# picoWiCopter.net
KiCad netlist of a schematic drawn in EAGLE
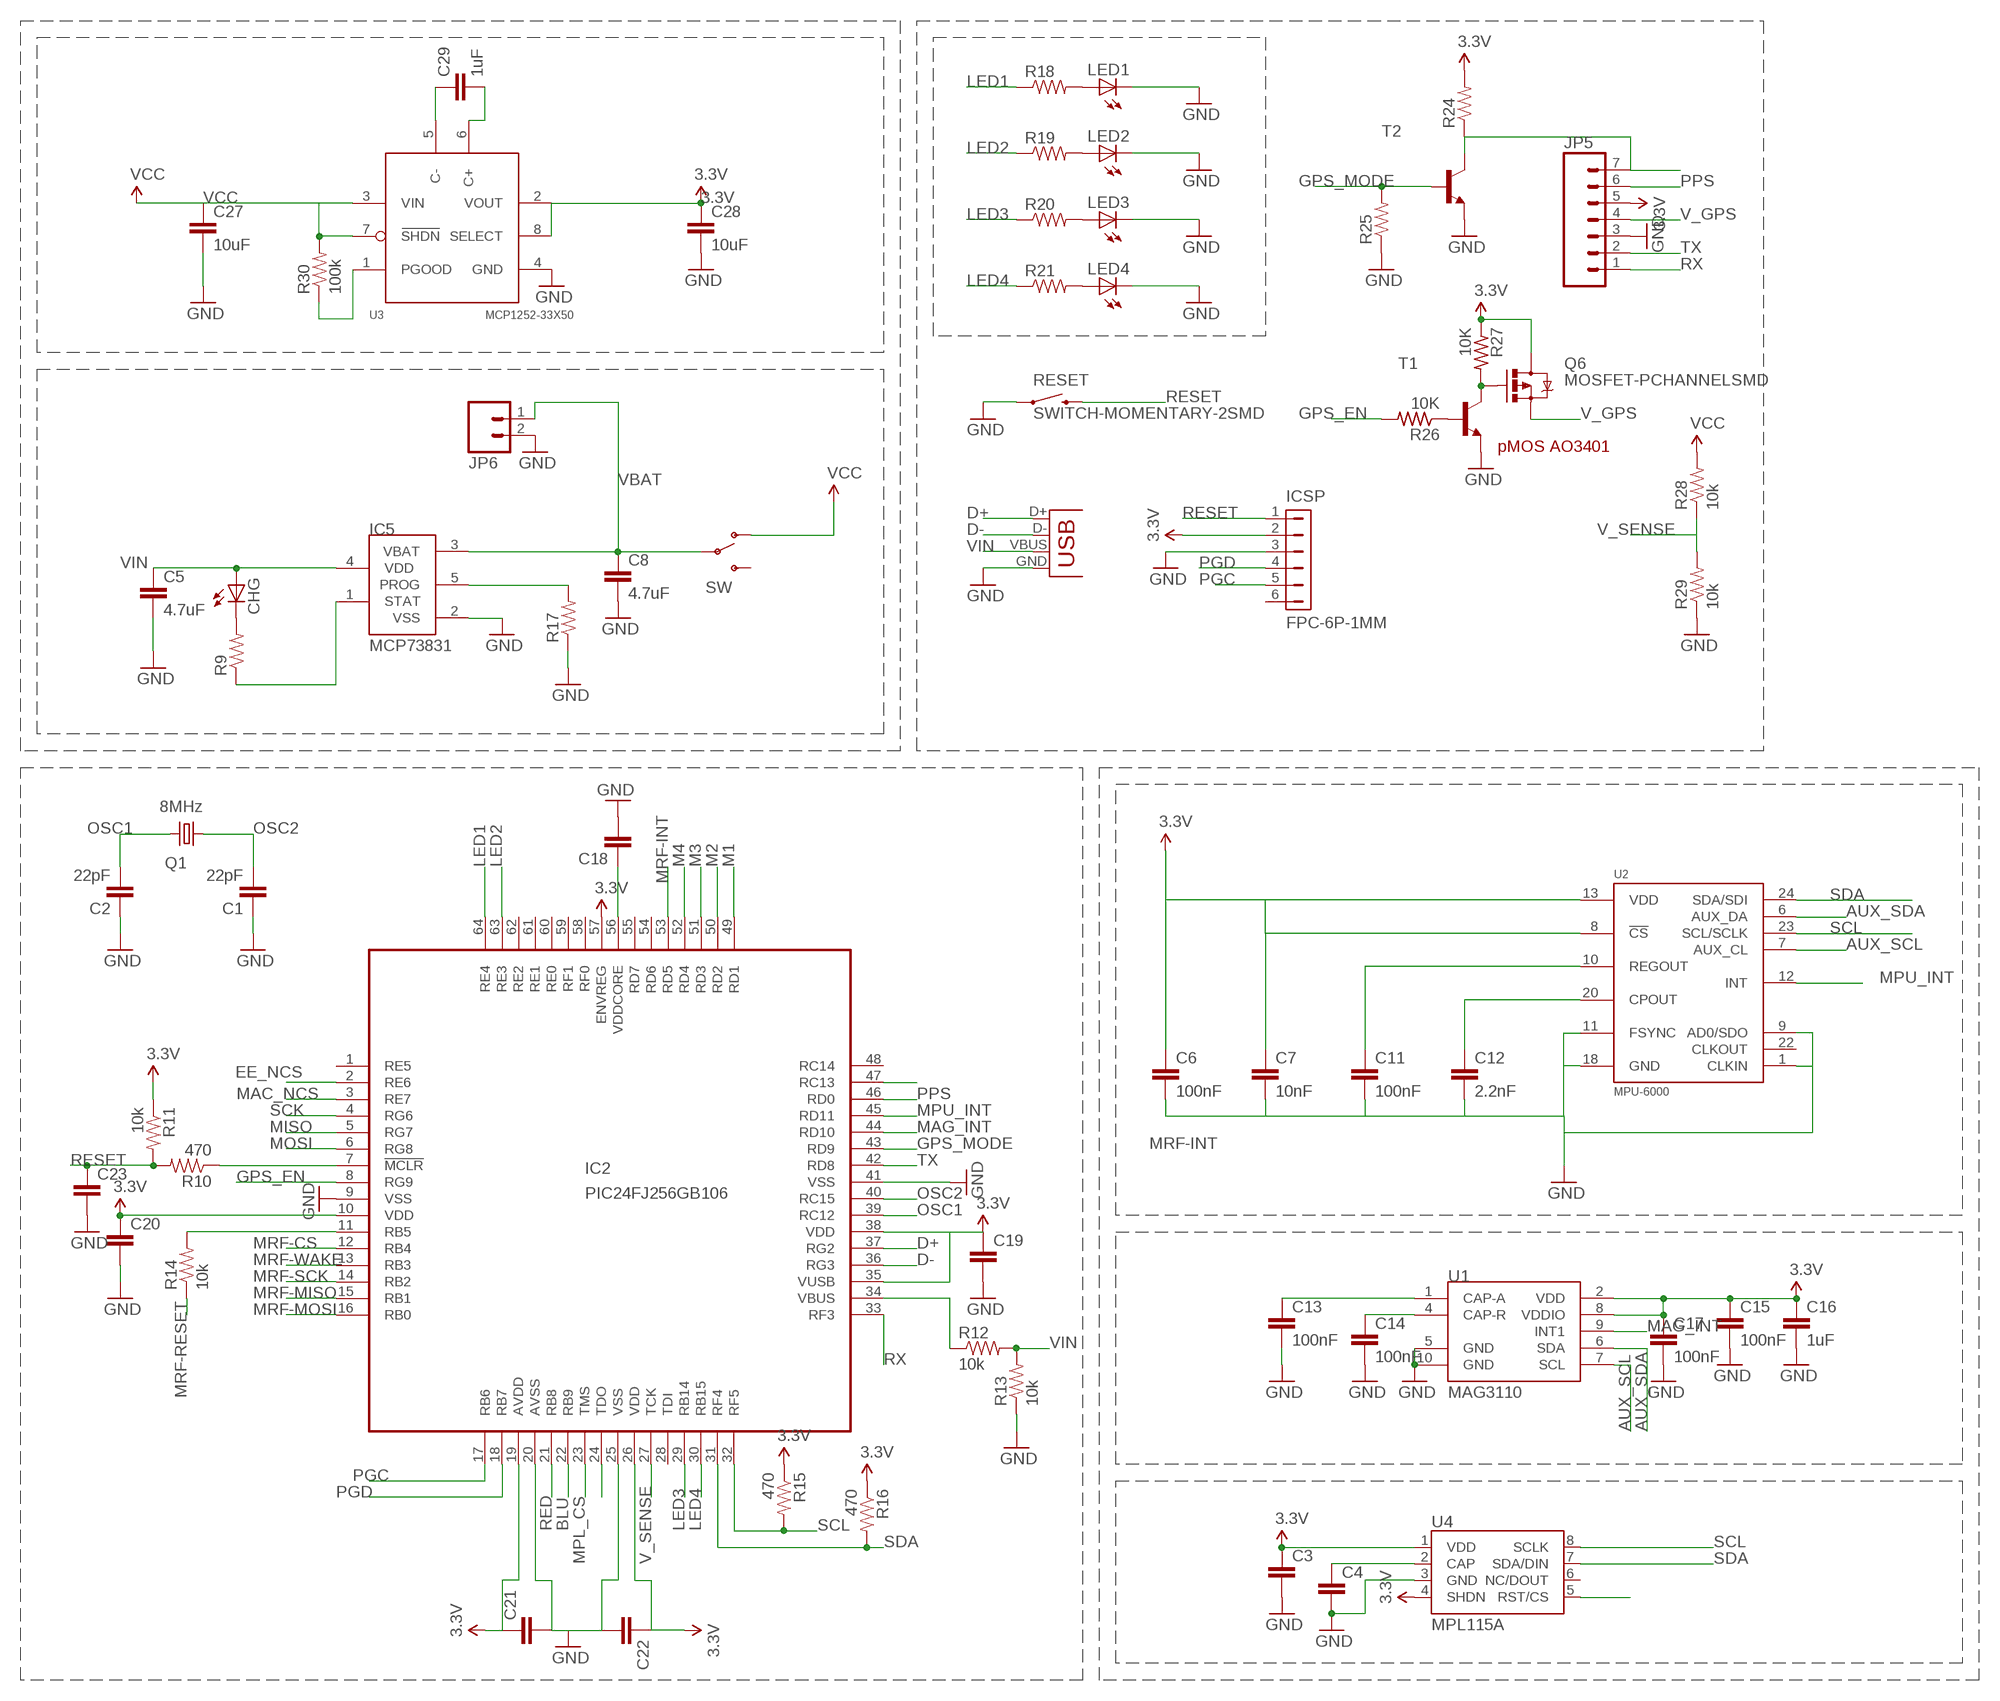
[diagram p0: schematic, sheet 1, part 1 of 2]
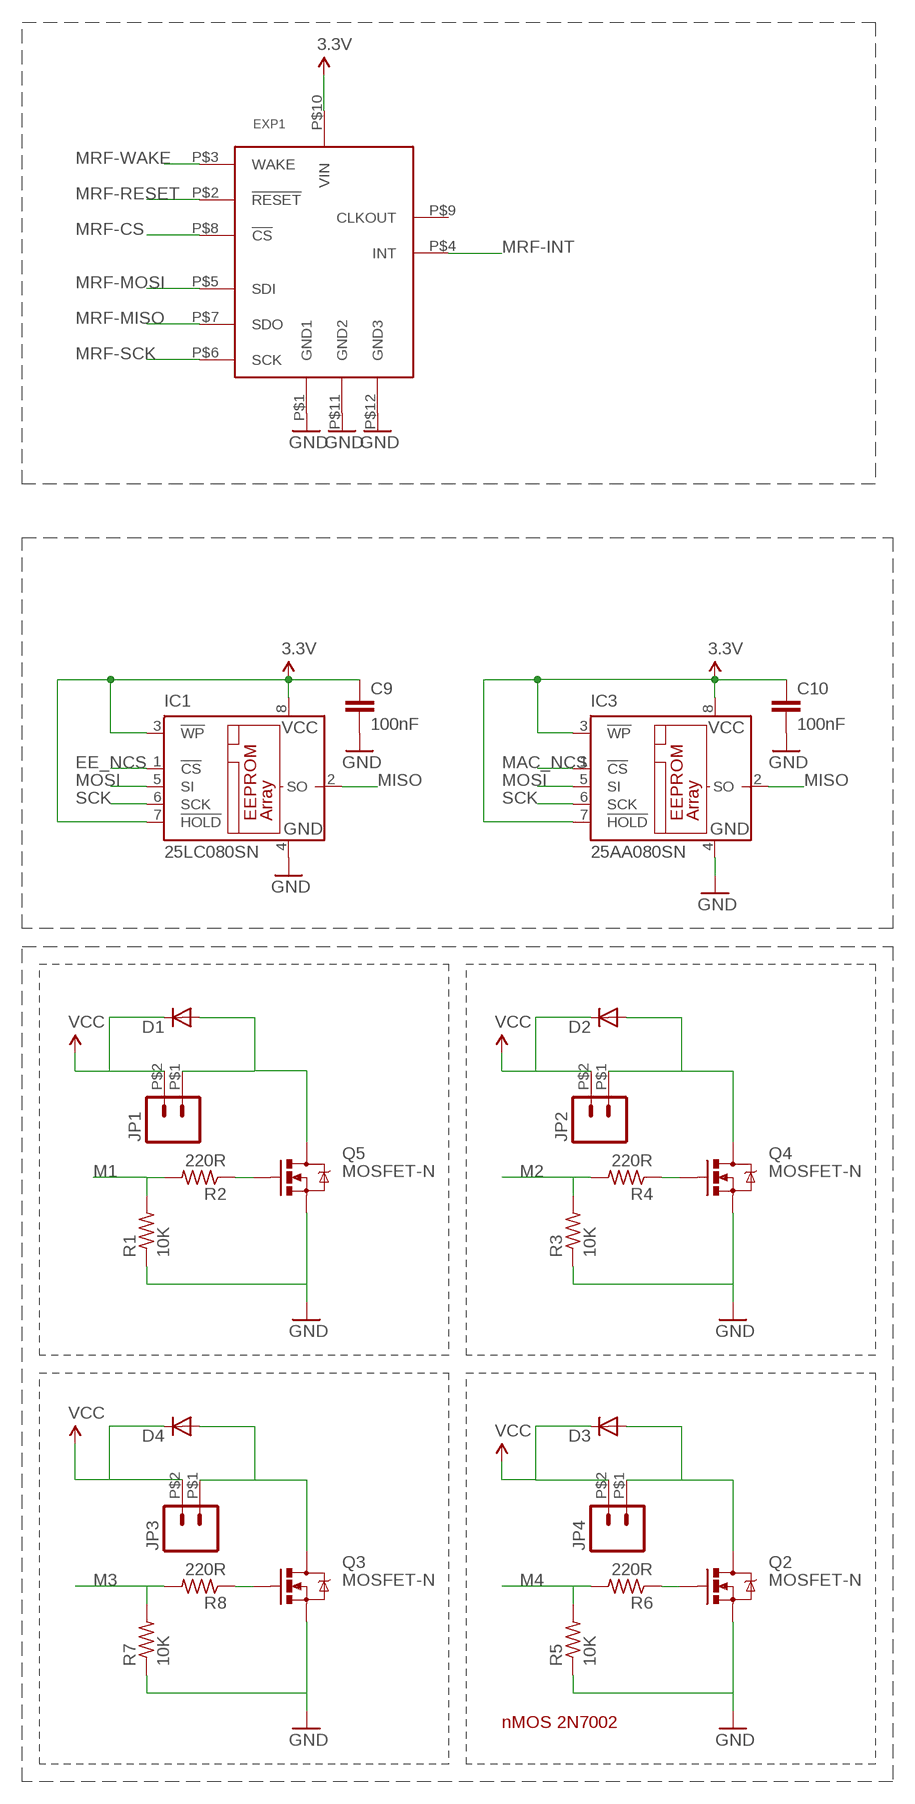
[diagram p1: schematic, sheet 1, part 2 of 2]

(export (version "E")
  (design (tool "Eeschema 10.0.6"))
  (components
    (comp (ref "C1")
      (value "22pF")
      (footprint "eagle-import:0603-CAP")
      (libsource (lib "eagle-import") (part "CAP0603-CAP"))
    )
    (comp (ref "C2")
      (value "22pF")
      (footprint "eagle-import:0603-CAP")
      (libsource (lib "eagle-import") (part "CAP0603-CAP"))
    )
    (comp (ref "C3")
      (value "CAP0603-CAP")
      (footprint "eagle-import:0603-CAP")
      (libsource (lib "eagle-import") (part "CAP0603-CAP"))
    )
    (comp (ref "C4")
      (value "CAP0603-CAP")
      (footprint "eagle-import:0603-CAP")
      (libsource (lib "eagle-import") (part "CAP0603-CAP"))
    )
    (comp (ref "C5")
      (value "4.7uF")
      (footprint "eagle-import:C1206")
      (libsource (lib "eagle-import") (part "C-EUC1206"))
    )
    (comp (ref "C6")
      (value "100nF")
      (footprint "eagle-import:0603-CAP")
      (libsource (lib "eagle-import") (part "CAP0603-CAP"))
    )
    (comp (ref "C7")
      (value "10nF")
      (footprint "eagle-import:0603-CAP")
      (libsource (lib "eagle-import") (part "CAP0603-CAP"))
    )
    (comp (ref "C8")
      (value "4.7uF")
      (footprint "eagle-import:C1206")
      (libsource (lib "eagle-import") (part "C-EUC1206"))
    )
    (comp (ref "C9")
      (value "100nF")
      (footprint "eagle-import:0603-CAP")
      (libsource (lib "eagle-import") (part "CAP0603-CAP"))
    )
    (comp (ref "C10")
      (value "100nF")
      (footprint "eagle-import:0603-CAP")
      (libsource (lib "eagle-import") (part "CAP0603-CAP"))
    )
    (comp (ref "C11")
      (value "100nF")
      (footprint "eagle-import:0603-CAP")
      (libsource (lib "eagle-import") (part "CAP0603-CAP"))
    )
    (comp (ref "C12")
      (value "2.2nF")
      (footprint "eagle-import:0603-CAP")
      (libsource (lib "eagle-import") (part "CAP0603-CAP"))
    )
    (comp (ref "C13")
      (value "100nF")
      (footprint "eagle-import:0603-CAP")
      (libsource (lib "eagle-import") (part "CAP0603-CAP"))
    )
    (comp (ref "C14")
      (value "100nF")
      (footprint "eagle-import:0603-CAP")
      (libsource (lib "eagle-import") (part "CAP0603-CAP"))
    )
    (comp (ref "C15")
      (value "100nF")
      (footprint "eagle-import:0603-CAP")
      (libsource (lib "eagle-import") (part "CAP0603-CAP"))
    )
    (comp (ref "C16")
      (value "1uF")
      (footprint "eagle-import:0603-CAP")
      (libsource (lib "eagle-import") (part "CAP0603-CAP"))
    )
    (comp (ref "C17")
      (value "100nF")
      (footprint "eagle-import:0603-CAP")
      (libsource (lib "eagle-import") (part "CAP0603-CAP"))
    )
    (comp (ref "C18")
      (value "CAP1206")
      (footprint "eagle-import:1206")
      (libsource (lib "eagle-import") (part "CAP1206"))
    )
    (comp (ref "C19")
      (value "CAP0603-CAP")
      (footprint "eagle-import:0603-CAP")
      (libsource (lib "eagle-import") (part "CAP0603-CAP"))
    )
    (comp (ref "C20")
      (value "CAP0603-CAP")
      (footprint "eagle-import:0603-CAP")
      (libsource (lib "eagle-import") (part "CAP0603-CAP"))
    )
    (comp (ref "C21")
      (value "CAP0603-CAP")
      (footprint "eagle-import:0603-CAP")
      (libsource (lib "eagle-import") (part "CAP0603-CAP"))
    )
    (comp (ref "C22")
      (value "CAP0603-CAP")
      (footprint "eagle-import:0603-CAP")
      (libsource (lib "eagle-import") (part "CAP0603-CAP"))
    )
    (comp (ref "C23")
      (value "CAP0603-CAP")
      (footprint "eagle-import:0603-CAP")
      (libsource (lib "eagle-import") (part "CAP0603-CAP"))
    )
    (comp (ref "C27")
      (value "10uF")
      (footprint "eagle-import:1206")
      (libsource (lib "eagle-import") (part "CAP1206"))
    )
    (comp (ref "C28")
      (value "10uF")
      (footprint "eagle-import:1206")
      (libsource (lib "eagle-import") (part "CAP1206"))
    )
    (comp (ref "C29")
      (value "1uF")
      (footprint "eagle-import:0603-CAP")
      (libsource (lib "eagle-import") (part "CAP0603-CAP"))
    )
    (comp (ref "CHG")
      (value "LEDCHIP-LED0603")
      (footprint "eagle-import:CHIP-LED0603")
      (libsource (lib "eagle-import") (part "LEDCHIP-LED0603"))
    )
    (comp (ref "D1")
      (value "DIODE-MINIMELF")
      (footprint "eagle-import:MINIMELF")
      (libsource (lib "eagle-import") (part "DIODE-MINIMELF"))
    )
    (comp (ref "D2")
      (value "DIODE-MINIMELF")
      (footprint "eagle-import:MINIMELF")
      (libsource (lib "eagle-import") (part "DIODE-MINIMELF"))
    )
    (comp (ref "D3")
      (value "DIODE-MINIMELF")
      (footprint "eagle-import:MINIMELF")
      (libsource (lib "eagle-import") (part "DIODE-MINIMELF"))
    )
    (comp (ref "D4")
      (value "DIODE-MINIMELF")
      (footprint "eagle-import:MINIMELF")
      (libsource (lib "eagle-import") (part "DIODE-MINIMELF"))
    )
    (comp (ref "EXP1")
      (value "MRF24J40MA\"")
      (footprint "eagle-import:MRF24J40MA")
      (libsource (lib "eagle-import") (part "MRF24J40MA{dblquote}"))
    )
    (comp (ref "IC1")
      (value "25LC080SN")
      (footprint "eagle-import:SO-08")
      (fields (field (name "MF") "MICROCHIP") (field (name "MPN") "25LC080/SN"))
      (libsource (lib "eagle-import") (part "25SNLC080"))
    )
    (comp (ref "IC2")
      (value "PIC24FJ256GB106")
      (footprint "eagle-import:TQFP64-10X10")
      (fields (field (name "MPN") "PIC24FJ256GB106-I/PT"))
      (libsource (lib "eagle-import") (part "PIC24FJ256GB106"))
    )
    (comp (ref "IC3")
      (value "25AA080SN")
      (footprint "eagle-import:SO-08")
      (fields (field (name "MF") "MICROCHIP") (field (name "MPN") "25AA080/SN"))
      (libsource (lib "eagle-import") (part "25SNAA080"))
    )
    (comp (ref "IC5")
      (value "MCP73831")
      (footprint "eagle-import:SOT23-5L")
      (libsource (lib "eagle-import") (part "MCP73831"))
    )
    (comp (ref "ICSP")
      (value "FPC-6P-1MM")
      (footprint "eagle-import:FPC-6P-1MM")
      (libsource (lib "eagle-import") (part "FPC-6P-1MM"))
    )
    (comp (ref "JP1")
      (value "M02")
      (footprint "eagle-import:1X2SMD")
      (libsource (lib "eagle-import") (part "M02"))
    )
    (comp (ref "JP2")
      (value "M02")
      (footprint "eagle-import:1X2SMD")
      (libsource (lib "eagle-import") (part "M02"))
    )
    (comp (ref "JP3")
      (value "M02")
      (footprint "eagle-import:1X2SMD")
      (libsource (lib "eagle-import") (part "M02"))
    )
    (comp (ref "JP4")
      (value "M02")
      (footprint "eagle-import:1X2SMD")
      (libsource (lib "eagle-import") (part "M02"))
    )
    (comp (ref "JP5")
      (value "M07")
      (footprint "eagle-import:1X07")
      (libsource (lib "eagle-import") (part "M07"))
    )
    (comp (ref "JP6")
      (value "M02PTH")
      (footprint "eagle-import:1X02")
      (libsource (lib "eagle-import") (part "M02PTH"))
    )
    (comp (ref "LED1")
      (value "LED0603")
      (footprint "eagle-import:LED-0603")
      (libsource (lib "eagle-import") (part "LED0603"))
    )
    (comp (ref "LED2")
      (value "LED0603")
      (footprint "eagle-import:LED-0603")
      (libsource (lib "eagle-import") (part "LED0603"))
    )
    (comp (ref "LED3")
      (value "LED0603")
      (footprint "eagle-import:LED-0603")
      (libsource (lib "eagle-import") (part "LED0603"))
    )
    (comp (ref "LED4")
      (value "LED0603")
      (footprint "eagle-import:LED-0603")
      (libsource (lib "eagle-import") (part "LED0603"))
    )
    (comp (ref "Q1")
      (value "8MHz")
      (footprint "eagle-import:CTS406")
      (libsource (lib "eagle-import") (part "CRYSTALCTS406"))
    )
    (comp (ref "Q2")
      (value "MOSFET-N")
      (footprint "eagle-import:SOT23-3")
      (libsource (lib "eagle-import") (part "MOSFET-NCHANNELSMD"))
    )
    (comp (ref "Q3")
      (value "MOSFET-N")
      (footprint "eagle-import:SOT23-3")
      (libsource (lib "eagle-import") (part "MOSFET-NCHANNELSMD"))
    )
    (comp (ref "Q4")
      (value "MOSFET-N")
      (footprint "eagle-import:SOT23-3")
      (libsource (lib "eagle-import") (part "MOSFET-NCHANNELSMD"))
    )
    (comp (ref "Q5")
      (value "MOSFET-N")
      (footprint "eagle-import:SOT23-3")
      (libsource (lib "eagle-import") (part "MOSFET-NCHANNELSMD"))
    )
    (comp (ref "Q6")
      (value "MOSFET-PCHANNELSMD")
      (footprint "eagle-import:SOT23-3")
      (libsource (lib "eagle-import") (part "MOSFET-PCHANNELSMD"))
    )
    (comp (ref "R1")
      (value "10K")
      (footprint "eagle-import:R0603")
      (libsource (lib "eagle-import") (part "R-US_R0603"))
    )
    (comp (ref "R2")
      (value "220R")
      (footprint "eagle-import:R0603")
      (libsource (lib "eagle-import") (part "R-US_R0603"))
    )
    (comp (ref "R3")
      (value "10K")
      (footprint "eagle-import:R0603")
      (libsource (lib "eagle-import") (part "R-US_R0603"))
    )
    (comp (ref "R4")
      (value "220R")
      (footprint "eagle-import:R0603")
      (libsource (lib "eagle-import") (part "R-US_R0603"))
    )
    (comp (ref "R5")
      (value "10K")
      (footprint "eagle-import:R0603")
      (libsource (lib "eagle-import") (part "R-US_R0603"))
    )
    (comp (ref "R6")
      (value "220R")
      (footprint "eagle-import:R0603")
      (libsource (lib "eagle-import") (part "R-US_R0603"))
    )
    (comp (ref "R7")
      (value "10K")
      (footprint "eagle-import:R0603")
      (libsource (lib "eagle-import") (part "R-US_R0603"))
    )
    (comp (ref "R8")
      (value "220R")
      (footprint "eagle-import:R0603")
      (libsource (lib "eagle-import") (part "R-US_R0603"))
    )
    (comp (ref "R9")
      (value "RESISTOR0603-RES")
      (footprint "eagle-import:0603-RES")
      (libsource (lib "eagle-import") (part "RESISTOR0603-RES"))
    )
    (comp (ref "R10")
      (value "470")
      (footprint "eagle-import:0603-RES")
      (libsource (lib "eagle-import") (part "RESISTOR0603-RES"))
    )
    (comp (ref "R11")
      (value "10k")
      (footprint "eagle-import:0603-RES")
      (libsource (lib "eagle-import") (part "RESISTOR0603-RES"))
    )
    (comp (ref "R12")
      (value "10k")
      (footprint "eagle-import:0603-RES")
      (libsource (lib "eagle-import") (part "RESISTOR0603-RES"))
    )
    (comp (ref "R13")
      (value "10k")
      (footprint "eagle-import:0603-RES")
      (libsource (lib "eagle-import") (part "RESISTOR0603-RES"))
    )
    (comp (ref "R14")
      (value "10k")
      (footprint "eagle-import:0603-RES")
      (libsource (lib "eagle-import") (part "RESISTOR0603-RES"))
    )
    (comp (ref "R15")
      (value "470")
      (footprint "eagle-import:0603-RES")
      (libsource (lib "eagle-import") (part "RESISTOR0603-RES"))
    )
    (comp (ref "R16")
      (value "470")
      (footprint "eagle-import:0603-RES")
      (libsource (lib "eagle-import") (part "RESISTOR0603-RES"))
    )
    (comp (ref "R17")
      (value "RESISTOR0603-RES")
      (footprint "eagle-import:0603-RES")
      (libsource (lib "eagle-import") (part "RESISTOR0603-RES"))
    )
    (comp (ref "R18")
      (value "RESISTOR0603-RES")
      (footprint "eagle-import:0603-RES")
      (libsource (lib "eagle-import") (part "RESISTOR0603-RES"))
    )
    (comp (ref "R19")
      (value "RESISTOR0603-RES")
      (footprint "eagle-import:0603-RES")
      (libsource (lib "eagle-import") (part "RESISTOR0603-RES"))
    )
    (comp (ref "R20")
      (value "RESISTOR0603-RES")
      (footprint "eagle-import:0603-RES")
      (libsource (lib "eagle-import") (part "RESISTOR0603-RES"))
    )
    (comp (ref "R21")
      (value "RESISTOR0603-RES")
      (footprint "eagle-import:0603-RES")
      (libsource (lib "eagle-import") (part "RESISTOR0603-RES"))
    )
    (comp (ref "R24")
      (value "RESISTOR0603-RES")
      (footprint "eagle-import:0603-RES")
      (libsource (lib "eagle-import") (part "RESISTOR0603-RES"))
    )
    (comp (ref "R25")
      (value "RESISTOR0603-RES")
      (footprint "eagle-import:0603-RES")
      (libsource (lib "eagle-import") (part "RESISTOR0603-RES"))
    )
    (comp (ref "R26")
      (value "10K")
      (footprint "eagle-import:R0603")
      (libsource (lib "eagle-import") (part "R-US_R0603"))
    )
    (comp (ref "R27")
      (value "10K")
      (footprint "eagle-import:R0603")
      (libsource (lib "eagle-import") (part "R-US_R0603"))
    )
    (comp (ref "R28")
      (value "10k")
      (footprint "eagle-import:0603-RES")
      (libsource (lib "eagle-import") (part "RESISTOR0603-RES"))
    )
    (comp (ref "R29")
      (value "10k")
      (footprint "eagle-import:0603-RES")
      (libsource (lib "eagle-import") (part "RESISTOR0603-RES"))
    )
    (comp (ref "R30")
      (value "100k")
      (footprint "eagle-import:0603-RES")
      (libsource (lib "eagle-import") (part "RESISTOR0603-RES"))
    )
    (comp (ref "RESET")
      (value "SWITCH-MOMENTARY-2SMD")
      (footprint "eagle-import:TACTILE_SWITCH_SMD")
      (libsource (lib "eagle-import") (part "SWITCH-MOMENTARY-2SMD"))
    )
    (comp (ref "SW")
      (value "SWITCH-SPDTPTH_LOCK")
      (footprint "eagle-import:SWITCH-SPDT_LOCK.007S")
      (libsource (lib "eagle-import") (part "SWITCH-SPDTPTH_LOCK"))
    )
    (comp (ref "T1")
      (value "BFR92-NPN-SOT23-BEC")
      (footprint "eagle-import:SOT23-BEC")
      (libsource (lib "eagle-import") (part "-NPN-SOT23-BECBFR92"))
    )
    (comp (ref "T2")
      (value "BFR92-NPN-SOT23-BEC")
      (footprint "eagle-import:SOT23-BEC")
      (libsource (lib "eagle-import") (part "-NPN-SOT23-BECBFR92"))
    )
    (comp (ref "U1")
      (value "MAG3110")
      (footprint "eagle-import:DFN-10")
      (libsource (lib "eagle-import") (part "MAG3110"))
    )
    (comp (ref "U2")
      (value "MPU-6000")
      (footprint "eagle-import:QFN-24")
      (libsource (lib "eagle-import") (part "MPU-6000"))
    )
    (comp (ref "U3")
      (value "MCP1252-33X50")
      (footprint "eagle-import:MSOP8")
      (libsource (lib "eagle-import") (part "MCP1252-33X50"))
    )
    (comp (ref "U4")
      (value "MPL115A")
      (footprint "eagle-import:LGA8")
      (libsource (lib "eagle-import") (part "MPL115A"))
    )
    (comp (ref "X3")
      (value "USBSMD")
      (footprint "eagle-import:USB-MINIB")
      (libsource (lib "eagle-import") (part "USBSMD"))
    )
  )
  (nets
    (net (code "1") (name "/AUX_SCL") (class "Default")
      (node (ref "U1") (pin "7") (pinfunction "SCL_7") (pintype "bidirectional"))
      (node (ref "U2") (pin "7") (pinfunction "AUX_CL_7") (pintype "bidirectional"))
    )
    (net (code "2") (name "/AUX_SDA") (class "Default")
      (node (ref "U1") (pin "6") (pinfunction "SDA_6") (pintype "bidirectional"))
      (node (ref "U2") (pin "6") (pinfunction "AUX_DA_6") (pintype "bidirectional"))
    )
    (net (code "3") (name "/BLU") (class "Default")
      (node (ref "IC2") (pin "22") (pinfunction "RB9_22") (pintype "bidirectional"))
    )
    (net (code "4") (name "/D+") (class "Default")
      (node (ref "IC2") (pin "37") (pinfunction "RG2_37") (pintype "bidirectional"))
      (node (ref "X3") (pin "D+") (pinfunction "D+_D+") (pintype "bidirectional"))
    )
    (net (code "5") (name "/D-") (class "Default")
      (node (ref "IC2") (pin "36") (pinfunction "RG3_36") (pintype "bidirectional"))
      (node (ref "X3") (pin "D-") (pinfunction "D-_D-") (pintype "bidirectional"))
    )
    (net (code "6") (name "/EE_NCS") (class "Default")
      (node (ref "IC1") (pin "1") (pinfunction "~{CS}_1") (pintype "input"))
      (node (ref "IC2") (pin "2") (pinfunction "RE6_2") (pintype "bidirectional"))
    )
    (net (code "7") (name "/GPS_EN") (class "Default")
      (node (ref "IC2") (pin "8") (pinfunction "RG9_8") (pintype "bidirectional"))
      (node (ref "R26") (pin "2") (pinfunction "2_2") (pintype "passive"))
    )
    (net (code "8") (name "/GPS_MODE") (class "Default")
      (node (ref "IC2") (pin "43") (pinfunction "RD9_43") (pintype "bidirectional"))
      (node (ref "R25") (pin "2") (pinfunction "2_2") (pintype "passive"))
      (node (ref "T2") (pin "B") (pinfunction "B_B") (pintype "passive"))
    )
    (net (code "9") (name "/LED1") (class "Default")
      (node (ref "IC2") (pin "64") (pinfunction "RE4_64") (pintype "bidirectional"))
      (node (ref "R18") (pin "1") (pinfunction "1_1") (pintype "passive"))
    )
    (net (code "10") (name "/LED2") (class "Default")
      (node (ref "IC2") (pin "63") (pinfunction "RE3_63") (pintype "bidirectional"))
      (node (ref "R19") (pin "1") (pinfunction "1_1") (pintype "passive"))
    )
    (net (code "11") (name "/LED3") (class "Default")
      (node (ref "IC2") (pin "29") (pinfunction "RB14_29") (pintype "bidirectional"))
      (node (ref "R20") (pin "1") (pinfunction "1_1") (pintype "passive"))
    )
    (net (code "12") (name "/LED4") (class "Default")
      (node (ref "IC2") (pin "30") (pinfunction "RB15_30") (pintype "bidirectional"))
      (node (ref "R21") (pin "1") (pinfunction "1_1") (pintype "passive"))
    )
    (net (code "13") (name "/M1") (class "Default")
      (node (ref "IC2") (pin "49") (pinfunction "RD1_49") (pintype "bidirectional"))
      (node (ref "R1") (pin "2") (pinfunction "2_2") (pintype "passive"))
      (node (ref "R2") (pin "2") (pinfunction "2_2") (pintype "passive"))
    )
    (net (code "14") (name "/M2") (class "Default")
      (node (ref "IC2") (pin "50") (pinfunction "RD2_50") (pintype "bidirectional"))
      (node (ref "R3") (pin "2") (pinfunction "2_2") (pintype "passive"))
      (node (ref "R4") (pin "2") (pinfunction "2_2") (pintype "passive"))
    )
    (net (code "15") (name "/M3") (class "Default")
      (node (ref "IC2") (pin "51") (pinfunction "RD3_51") (pintype "bidirectional"))
      (node (ref "R7") (pin "2") (pinfunction "2_2") (pintype "passive"))
      (node (ref "R8") (pin "2") (pinfunction "2_2") (pintype "passive"))
    )
    (net (code "16") (name "/M4") (class "Default")
      (node (ref "IC2") (pin "52") (pinfunction "RD4_52") (pintype "bidirectional"))
      (node (ref "R5") (pin "2") (pinfunction "2_2") (pintype "passive"))
      (node (ref "R6") (pin "2") (pinfunction "2_2") (pintype "passive"))
    )
    (net (code "17") (name "/MAC_NCS") (class "Default")
      (node (ref "IC2") (pin "3") (pinfunction "RE7_3") (pintype "bidirectional"))
      (node (ref "IC3") (pin "1") (pinfunction "~{CS}_1") (pintype "input"))
    )
    (net (code "18") (name "/MAG_INT") (class "Default")
      (node (ref "IC2") (pin "44") (pinfunction "RD10_44") (pintype "bidirectional"))
      (node (ref "U1") (pin "9") (pinfunction "INT1_9") (pintype "bidirectional"))
    )
    (net (code "19") (name "/MISO") (class "Default")
      (node (ref "IC1") (pin "2") (pinfunction "SO_2") (pintype "bidirectional"))
      (node (ref "IC2") (pin "5") (pinfunction "RG7_5") (pintype "bidirectional"))
      (node (ref "IC3") (pin "2") (pinfunction "SO_2") (pintype "bidirectional"))
    )
    (net (code "20") (name "/MOSI") (class "Default")
      (node (ref "IC1") (pin "5") (pinfunction "SI_5") (pintype "input"))
      (node (ref "IC2") (pin "6") (pinfunction "RG8_6") (pintype "bidirectional"))
      (node (ref "IC3") (pin "5") (pinfunction "SI_5") (pintype "input"))
    )
    (net (code "21") (name "/MPL_CS") (class "Default")
      (node (ref "IC2") (pin "23") (pinfunction "TMS_23") (pintype "input"))
      (node (ref "U4") (pin "5") (pinfunction "RST/CS_5") (pintype "bidirectional"))
    )
    (net (code "22") (name "/MPU_INT") (class "Default")
      (node (ref "IC2") (pin "45") (pinfunction "RD11_45") (pintype "bidirectional"))
      (node (ref "U2") (pin "12") (pinfunction "INT_12") (pintype "bidirectional"))
    )
    (net (code "23") (name "/MRF-CS") (class "Default")
      (node (ref "EXP1") (pin "P$8") (pinfunction "~{CS}_P$8") (pintype "bidirectional"))
      (node (ref "IC2") (pin "12") (pinfunction "RB4_12") (pintype "bidirectional"))
    )
    (net (code "24") (name "/MRF-INT") (class "Default")
      (node (ref "EXP1") (pin "P$4") (pinfunction "INT_P$4") (pintype "bidirectional"))
      (node (ref "IC2") (pin "53") (pinfunction "RD5_53") (pintype "bidirectional"))
    )
    (net (code "25") (name "/MRF-MISO") (class "Default")
      (node (ref "EXP1") (pin "P$7") (pinfunction "SDO_P$7") (pintype "bidirectional"))
      (node (ref "IC2") (pin "15") (pinfunction "RB1_15") (pintype "bidirectional"))
    )
    (net (code "26") (name "/MRF-MOSI") (class "Default")
      (node (ref "EXP1") (pin "P$5") (pinfunction "SDI_P$5") (pintype "bidirectional"))
      (node (ref "IC2") (pin "16") (pinfunction "RB0_16") (pintype "bidirectional"))
    )
    (net (code "27") (name "/MRF-RESET") (class "Default")
      (node (ref "EXP1") (pin "P$2") (pinfunction "~{RESET}_P$2") (pintype "bidirectional"))
      (node (ref "R14") (pin "1") (pinfunction "1_1") (pintype "passive"))
    )
    (net (code "28") (name "/MRF-SCK") (class "Default")
      (node (ref "EXP1") (pin "P$6") (pinfunction "SCK_P$6") (pintype "bidirectional"))
      (node (ref "IC2") (pin "14") (pinfunction "RB2_14") (pintype "bidirectional"))
    )
    (net (code "29") (name "/MRF-WAKE") (class "Default")
      (node (ref "EXP1") (pin "P$3") (pinfunction "WAKE_P$3") (pintype "bidirectional"))
      (node (ref "IC2") (pin "13") (pinfunction "RB3_13") (pintype "bidirectional"))
    )
    (net (code "30") (name "/OSC1") (class "Default")
      (node (ref "C2") (pin "2") (pinfunction "2_2") (pintype "passive"))
      (node (ref "IC2") (pin "39") (pinfunction "RC12_39") (pintype "bidirectional"))
      (node (ref "Q1") (pin "3") (pinfunction "2_3") (pintype "passive"))
    )
    (net (code "31") (name "/OSC2") (class "Default")
      (node (ref "C1") (pin "2") (pinfunction "2_2") (pintype "passive"))
      (node (ref "IC2") (pin "40") (pinfunction "RC15_40") (pintype "bidirectional"))
      (node (ref "Q1") (pin "1") (pinfunction "1_1") (pintype "passive"))
    )
    (net (code "32") (name "/PGC") (class "Default")
      (node (ref "IC2") (pin "17") (pinfunction "RB6_17") (pintype "bidirectional"))
      (node (ref "ICSP") (pin "5") (pinfunction "5_5") (pintype "passive"))
    )
    (net (code "33") (name "/PGD") (class "Default")
      (node (ref "IC2") (pin "18") (pinfunction "RB7_18") (pintype "bidirectional"))
      (node (ref "ICSP") (pin "4") (pinfunction "4_4") (pintype "passive"))
    )
    (net (code "34") (name "/PPS") (class "Default")
      (node (ref "IC2") (pin "46") (pinfunction "RD0_46") (pintype "bidirectional"))
      (node (ref "JP5") (pin "6") (pinfunction "6_6") (pintype "passive"))
    )
    (net (code "35") (name "/RED") (class "Default")
      (node (ref "IC2") (pin "21") (pinfunction "RB8_21") (pintype "bidirectional"))
    )
    (net (code "36") (name "/RESET") (class "Default")
      (node (ref "C23") (pin "1") (pinfunction "1_1") (pintype "passive"))
      (node (ref "ICSP") (pin "1") (pinfunction "1_1") (pintype "passive"))
      (node (ref "R10") (pin "2") (pinfunction "2_2") (pintype "passive"))
      (node (ref "R11") (pin "2") (pinfunction "2_2") (pintype "passive"))
      (node (ref "RESET") (pin "3") (pinfunction "2_3") (pintype "passive"))
    )
    (net (code "37") (name "/RX") (class "Default")
      (node (ref "IC2") (pin "33") (pinfunction "RF3_33") (pintype "bidirectional"))
      (node (ref "JP5") (pin "1") (pinfunction "1_1") (pintype "passive"))
    )
    (net (code "38") (name "/SCK") (class "Default")
      (node (ref "IC1") (pin "6") (pinfunction "SCK_6") (pintype "input"))
      (node (ref "IC2") (pin "4") (pinfunction "RG6_4") (pintype "bidirectional"))
      (node (ref "IC3") (pin "6") (pinfunction "SCK_6") (pintype "input"))
    )
    (net (code "39") (name "/SCL") (class "Default")
      (node (ref "IC2") (pin "32") (pinfunction "RF5_32") (pintype "bidirectional"))
      (node (ref "R15") (pin "2") (pinfunction "2_2") (pintype "passive"))
      (node (ref "U2") (pin "23") (pinfunction "SCL/SCLK_23") (pintype "bidirectional"))
      (node (ref "U4") (pin "8") (pinfunction "SCLK_8") (pintype "bidirectional"))
    )
    (net (code "40") (name "/SDA") (class "Default")
      (node (ref "IC2") (pin "31") (pinfunction "RF4_31") (pintype "bidirectional"))
      (node (ref "R16") (pin "2") (pinfunction "2_2") (pintype "passive"))
      (node (ref "U2") (pin "24") (pinfunction "SDA/SDI_24") (pintype "bidirectional"))
      (node (ref "U4") (pin "7") (pinfunction "SDA/DIN_7") (pintype "bidirectional"))
    )
    (net (code "41") (name "/TX") (class "Default")
      (node (ref "IC2") (pin "42") (pinfunction "RD8_42") (pintype "bidirectional"))
      (node (ref "JP5") (pin "2") (pinfunction "2_2") (pintype "passive"))
    )
    (net (code "42") (name "/VIN") (class "Default")
      (node (ref "C5") (pin "1") (pinfunction "1_1") (pintype "passive"))
      (node (ref "CHG") (pin "A") (pinfunction "A_A") (pintype "passive"))
      (node (ref "IC5") (pin "4") (pinfunction "VDD_4") (pintype "bidirectional"))
      (node (ref "R12") (pin "2") (pinfunction "2_2") (pintype "passive"))
      (node (ref "R13") (pin "2") (pinfunction "2_2") (pintype "passive"))
      (node (ref "X3") (pin "VBUS") (pinfunction "VBUS_VBUS") (pintype "bidirectional"))
    )
    (net (code "43") (name "/V_GPS") (class "Default")
      (node (ref "JP5") (pin "4") (pinfunction "4_4") (pintype "passive"))
      (node (ref "Q6") (pin "2") (pinfunction "S_2") (pintype "passive"))
    )
    (net (code "44") (name "/V_SENSE") (class "Default")
      (node (ref "IC2") (pin "27") (pinfunction "TCK_27") (pintype "input"))
      (node (ref "R28") (pin "1") (pinfunction "1_1") (pintype "passive"))
      (node (ref "R29") (pin "2") (pinfunction "2_2") (pintype "passive"))
    )
    (net (code "45") (name "3.3V") (class "Default")
      (node (ref "C10") (pin "1") (pinfunction "1_1") (pintype "passive"))
      (node (ref "C15") (pin "1") (pinfunction "1_1") (pintype "passive"))
      (node (ref "C16") (pin "1") (pinfunction "1_1") (pintype "passive"))
      (node (ref "C17") (pin "1") (pinfunction "1_1") (pintype "passive"))
      (node (ref "C19") (pin "1") (pinfunction "1_1") (pintype "passive"))
      (node (ref "C20") (pin "1") (pinfunction "1_1") (pintype "passive"))
      (node (ref "C21") (pin "1") (pinfunction "1_1") (pintype "passive"))
      (node (ref "C22") (pin "1") (pinfunction "1_1") (pintype "passive"))
      (node (ref "C28") (pin "1") (pinfunction "1_1") (pintype "passive"))
      (node (ref "C3") (pin "1") (pinfunction "1_1") (pintype "passive"))
      (node (ref "C6") (pin "1") (pinfunction "1_1") (pintype "passive"))
      (node (ref "C7") (pin "1") (pinfunction "1_1") (pintype "passive"))
      (node (ref "C9") (pin "1") (pinfunction "1_1") (pintype "passive"))
      (node (ref "EXP1") (pin "P$10") (pinfunction "VIN_P$10") (pintype "bidirectional"))
      (node (ref "IC1") (pin "3") (pinfunction "~{WP}_3") (pintype "input"))
      (node (ref "IC1") (pin "7") (pinfunction "~{HOLD}_7") (pintype "input"))
      (node (ref "IC1") (pin "8") (pinfunction "VCC_8") (pintype "power_in"))
      (node (ref "IC2") (pin "10") (pinfunction "VDD_10") (pintype "power_in"))
      (node (ref "IC2") (pin "19") (pinfunction "AVDD_19") (pintype "power_in"))
      (node (ref "IC2") (pin "26") (pinfunction "VDD_26") (pintype "power_in"))
      (node (ref "IC2") (pin "35") (pinfunction "VUSB_35") (pintype "passive"))
      (node (ref "IC2") (pin "38") (pinfunction "VDD_38") (pintype "power_in"))
      (node (ref "IC2") (pin "57") (pinfunction "ENVREG_57") (pintype "passive"))
      (node (ref "IC3") (pin "3") (pinfunction "~{WP}_3") (pintype "input"))
      (node (ref "IC3") (pin "7") (pinfunction "~{HOLD}_7") (pintype "input"))
      (node (ref "IC3") (pin "8") (pinfunction "VCC_8") (pintype "power_in"))
      (node (ref "ICSP") (pin "2") (pinfunction "2_2") (pintype "passive"))
      (node (ref "JP5") (pin "5") (pinfunction "5_5") (pintype "passive"))
      (node (ref "Q6") (pin "3") (pinfunction "D_3") (pintype "passive"))
      (node (ref "R11") (pin "1") (pinfunction "1_1") (pintype "passive"))
      (node (ref "R15") (pin "1") (pinfunction "1_1") (pintype "passive"))
      (node (ref "R16") (pin "1") (pinfunction "1_1") (pintype "passive"))
      (node (ref "R24") (pin "2") (pinfunction "2_2") (pintype "passive"))
      (node (ref "R27") (pin "1") (pinfunction "1_1") (pintype "passive"))
      (node (ref "U1") (pin "2") (pinfunction "VDD_2") (pintype "bidirectional"))
      (node (ref "U1") (pin "8") (pinfunction "VDDIO_8") (pintype "bidirectional"))
      (node (ref "U2") (pin "13") (pinfunction "VDD_13") (pintype "bidirectional"))
      (node (ref "U2") (pin "8") (pinfunction "~{CS}_8") (pintype "bidirectional"))
      (node (ref "U3") (pin "2") (pinfunction "VOUT_2") (pintype "output"))
      (node (ref "U3") (pin "8") (pinfunction "SELECT_8") (pintype "input"))
      (node (ref "U4") (pin "1") (pinfunction "VDD_1") (pintype "bidirectional"))
      (node (ref "U4") (pin "4") (pinfunction "SHDN_4") (pintype "bidirectional"))
    )
    (net (code "46") (name "GND") (class "Default")
      (node (ref "C1") (pin "1") (pinfunction "1_1") (pintype "passive"))
      (node (ref "C10") (pin "2") (pinfunction "2_2") (pintype "passive"))
      (node (ref "C11") (pin "2") (pinfunction "2_2") (pintype "passive"))
      (node (ref "C12") (pin "2") (pinfunction "2_2") (pintype "passive"))
      (node (ref "C13") (pin "2") (pinfunction "2_2") (pintype "passive"))
      (node (ref "C14") (pin "2") (pinfunction "2_2") (pintype "passive"))
      (node (ref "C15") (pin "2") (pinfunction "2_2") (pintype "passive"))
      (node (ref "C16") (pin "2") (pinfunction "2_2") (pintype "passive"))
      (node (ref "C17") (pin "2") (pinfunction "2_2") (pintype "passive"))
      (node (ref "C18") (pin "2") (pinfunction "2_2") (pintype "passive"))
      (node (ref "C19") (pin "2") (pinfunction "2_2") (pintype "passive"))
      (node (ref "C2") (pin "1") (pinfunction "1_1") (pintype "passive"))
      (node (ref "C20") (pin "2") (pinfunction "2_2") (pintype "passive"))
      (node (ref "C21") (pin "2") (pinfunction "2_2") (pintype "passive"))
      (node (ref "C22") (pin "2") (pinfunction "2_2") (pintype "passive"))
      (node (ref "C23") (pin "2") (pinfunction "2_2") (pintype "passive"))
      (node (ref "C27") (pin "2") (pinfunction "2_2") (pintype "passive"))
      (node (ref "C28") (pin "2") (pinfunction "2_2") (pintype "passive"))
      (node (ref "C3") (pin "2") (pinfunction "2_2") (pintype "passive"))
      (node (ref "C4") (pin "2") (pinfunction "2_2") (pintype "passive"))
      (node (ref "C5") (pin "2") (pinfunction "2_2") (pintype "passive"))
      (node (ref "C6") (pin "2") (pinfunction "2_2") (pintype "passive"))
      (node (ref "C7") (pin "2") (pinfunction "2_2") (pintype "passive"))
      (node (ref "C8") (pin "2") (pinfunction "2_2") (pintype "passive"))
      (node (ref "C9") (pin "2") (pinfunction "2_2") (pintype "passive"))
      (node (ref "EXP1") (pin "P$1") (pinfunction "GND1_P$1") (pintype "power_in"))
      (node (ref "EXP1") (pin "P$11") (pinfunction "GND2_P$11") (pintype "power_in"))
      (node (ref "EXP1") (pin "P$12") (pinfunction "GND3_P$12") (pintype "power_in"))
      (node (ref "IC1") (pin "4") (pinfunction "GND_4") (pintype "power_in"))
      (node (ref "IC2") (pin "20") (pinfunction "AVSS_20") (pintype "power_in"))
      (node (ref "IC2") (pin "25") (pinfunction "VSS_25") (pintype "power_in"))
      (node (ref "IC2") (pin "41") (pinfunction "VSS_41") (pintype "power_in"))
      (node (ref "IC2") (pin "9") (pinfunction "VSS_9") (pintype "power_in"))
      (node (ref "IC3") (pin "4") (pinfunction "GND_4") (pintype "power_in"))
      (node (ref "IC5") (pin "2") (pinfunction "VSS_2") (pintype "bidirectional"))
      (node (ref "ICSP") (pin "3") (pinfunction "3_3") (pintype "passive"))
      (node (ref "JP5") (pin "3") (pinfunction "3_3") (pintype "passive"))
      (node (ref "JP6") (pin "2") (pinfunction "2_2") (pintype "passive"))
      (node (ref "LED1") (pin "C") (pinfunction "C_C") (pintype "passive"))
      (node (ref "LED2") (pin "C") (pinfunction "C_C") (pintype "passive"))
      (node (ref "LED3") (pin "C") (pinfunction "C_C") (pintype "passive"))
      (node (ref "LED4") (pin "C") (pinfunction "C_C") (pintype "passive"))
      (node (ref "Q2") (pin "2") (pinfunction "S_2") (pintype "passive"))
      (node (ref "Q3") (pin "2") (pinfunction "S_2") (pintype "passive"))
      (node (ref "Q4") (pin "2") (pinfunction "S_2") (pintype "passive"))
      (node (ref "Q5") (pin "2") (pinfunction "S_2") (pintype "passive"))
      (node (ref "R1") (pin "1") (pinfunction "1_1") (pintype "passive"))
      (node (ref "R13") (pin "1") (pinfunction "1_1") (pintype "passive"))
      (node (ref "R17") (pin "1") (pinfunction "1_1") (pintype "passive"))
      (node (ref "R25") (pin "1") (pinfunction "1_1") (pintype "passive"))
      (node (ref "R29") (pin "1") (pinfunction "1_1") (pintype "passive"))
      (node (ref "R3") (pin "1") (pinfunction "1_1") (pintype "passive"))
      (node (ref "R5") (pin "1") (pinfunction "1_1") (pintype "passive"))
      (node (ref "R7") (pin "1") (pinfunction "1_1") (pintype "passive"))
      (node (ref "RESET") (pin "1") (pinfunction "1_1") (pintype "passive"))
      (node (ref "T1") (pin "E") (pinfunction "E_E") (pintype "passive"))
      (node (ref "T2") (pin "E") (pinfunction "E_E") (pintype "passive"))
      (node (ref "U1") (pin "10") (pinfunction "GND_10") (pintype "bidirectional"))
      (node (ref "U1") (pin "5") (pinfunction "GND_5") (pintype "bidirectional"))
      (node (ref "U2") (pin "1") (pinfunction "CLKIN_1") (pintype "bidirectional"))
      (node (ref "U2") (pin "11") (pinfunction "FSYNC_11") (pintype "bidirectional"))
      (node (ref "U2") (pin "18") (pinfunction "GND_18") (pintype "bidirectional"))
      (node (ref "U2") (pin "9") (pinfunction "AD0/SDO_9") (pintype "bidirectional"))
      (node (ref "U3") (pin "4") (pinfunction "GND_4") (pintype "power_in"))
      (node (ref "U4") (pin "3") (pinfunction "GND_3") (pintype "bidirectional"))
      (node (ref "X3") (pin "GND") (pinfunction "GND_GND") (pintype "bidirectional"))
    )
    (net (code "47") (name "Net-(CHG-PadC)") (class "Default")
      (node (ref "CHG") (pin "C") (pinfunction "C_C") (pintype "passive"))
      (node (ref "R9") (pin "2") (pinfunction "2_2") (pintype "passive"))
    )
    (net (code "48") (name "Net-(IC2-RB5)") (class "Default")
      (node (ref "IC2") (pin "11") (pinfunction "RB5_11") (pintype "bidirectional"))
      (node (ref "R14") (pin "2") (pinfunction "2_2") (pintype "passive"))
    )
    (net (code "49") (name "Net-(IC2-VBUS)") (class "Default")
      (node (ref "IC2") (pin "34") (pinfunction "VBUS_34") (pintype "passive"))
      (node (ref "R12") (pin "1") (pinfunction "1_1") (pintype "passive"))
    )
    (net (code "50") (name "Net-(IC2-VDDCORE)") (class "Default")
      (node (ref "C18") (pin "1") (pinfunction "1_1") (pintype "passive"))
      (node (ref "IC2") (pin "56") (pinfunction "VDDCORE_56") (pintype "power_in"))
    )
    (net (code "51") (name "Net-(IC2-~{MCLR})") (class "Default")
      (node (ref "IC2") (pin "7") (pinfunction "~{MCLR}_7") (pintype "bidirectional"))
      (node (ref "R10") (pin "1") (pinfunction "1_1") (pintype "passive"))
    )
    (net (code "52") (name "Net-(IC5-PROG)") (class "Default")
      (node (ref "IC5") (pin "5") (pinfunction "PROG_5") (pintype "bidirectional"))
      (node (ref "R17") (pin "2") (pinfunction "2_2") (pintype "passive"))
    )
    (net (code "53") (name "Net-(IC5-STAT)") (class "Default")
      (node (ref "IC5") (pin "1") (pinfunction "STAT_1") (pintype "bidirectional"))
      (node (ref "R9") (pin "1") (pinfunction "1_1") (pintype "passive"))
    )
    (net (code "54") (name "Net-(IC5-VBAT)") (class "Default")
      (node (ref "C8") (pin "1") (pinfunction "1_1") (pintype "passive"))
      (node (ref "IC5") (pin "3") (pinfunction "VBAT_3") (pintype "bidirectional"))
      (node (ref "JP6") (pin "1") (pinfunction "1_1") (pintype "passive"))
      (node (ref "SW") (pin "2") (pinfunction "P_2") (pintype "passive"))
    )
    (net (code "55") (name "Net-(JP1-1)") (class "Default")
      (node (ref "D1") (pin "A") (pinfunction "A_A") (pintype "passive"))
      (node (ref "JP1") (pin "P$1") (pinfunction "1_P$1") (pintype "passive"))
      (node (ref "Q5") (pin "3") (pinfunction "D_3") (pintype "passive"))
    )
    (net (code "56") (name "Net-(JP2-1)") (class "Default")
      (node (ref "D2") (pin "A") (pinfunction "A_A") (pintype "passive"))
      (node (ref "JP2") (pin "P$1") (pinfunction "1_P$1") (pintype "passive"))
      (node (ref "Q4") (pin "3") (pinfunction "D_3") (pintype "passive"))
    )
    (net (code "57") (name "Net-(JP3-1)") (class "Default")
      (node (ref "D4") (pin "A") (pinfunction "A_A") (pintype "passive"))
      (node (ref "JP3") (pin "P$1") (pinfunction "1_P$1") (pintype "passive"))
      (node (ref "Q3") (pin "3") (pinfunction "D_3") (pintype "passive"))
    )
    (net (code "58") (name "Net-(JP4-1)") (class "Default")
      (node (ref "D3") (pin "A") (pinfunction "A_A") (pintype "passive"))
      (node (ref "JP4") (pin "P$1") (pinfunction "1_P$1") (pintype "passive"))
      (node (ref "Q2") (pin "3") (pinfunction "D_3") (pintype "passive"))
    )
    (net (code "59") (name "Net-(JP5-Pad7)") (class "Default")
      (node (ref "JP5") (pin "7") (pinfunction "7_7") (pintype "passive"))
      (node (ref "R24") (pin "1") (pinfunction "1_1") (pintype "passive"))
      (node (ref "T2") (pin "C") (pinfunction "C_C") (pintype "passive"))
    )
    (net (code "60") (name "Net-(LED1-PadA)") (class "Default")
      (node (ref "LED1") (pin "A") (pinfunction "A_A") (pintype "passive"))
      (node (ref "R18") (pin "2") (pinfunction "2_2") (pintype "passive"))
    )
    (net (code "61") (name "Net-(LED2-PadA)") (class "Default")
      (node (ref "LED2") (pin "A") (pinfunction "A_A") (pintype "passive"))
      (node (ref "R19") (pin "2") (pinfunction "2_2") (pintype "passive"))
    )
    (net (code "62") (name "Net-(LED3-PadA)") (class "Default")
      (node (ref "LED3") (pin "A") (pinfunction "A_A") (pintype "passive"))
      (node (ref "R20") (pin "2") (pinfunction "2_2") (pintype "passive"))
    )
    (net (code "63") (name "Net-(LED4-PadA)") (class "Default")
      (node (ref "LED4") (pin "A") (pinfunction "A_A") (pintype "passive"))
      (node (ref "R21") (pin "2") (pinfunction "2_2") (pintype "passive"))
    )
    (net (code "64") (name "Net-(Q2-G)") (class "Default")
      (node (ref "Q2") (pin "1") (pinfunction "G_1") (pintype "passive"))
      (node (ref "R6") (pin "1") (pinfunction "1_1") (pintype "passive"))
    )
    (net (code "65") (name "Net-(Q3-G)") (class "Default")
      (node (ref "Q3") (pin "1") (pinfunction "G_1") (pintype "passive"))
      (node (ref "R8") (pin "1") (pinfunction "1_1") (pintype "passive"))
    )
    (net (code "66") (name "Net-(Q4-G)") (class "Default")
      (node (ref "Q4") (pin "1") (pinfunction "G_1") (pintype "passive"))
      (node (ref "R4") (pin "1") (pinfunction "1_1") (pintype "passive"))
    )
    (net (code "67") (name "Net-(Q5-G)") (class "Default")
      (node (ref "Q5") (pin "1") (pinfunction "G_1") (pintype "passive"))
      (node (ref "R2") (pin "1") (pinfunction "1_1") (pintype "passive"))
    )
    (net (code "68") (name "Net-(Q6-G)") (class "Default")
      (node (ref "Q6") (pin "1") (pinfunction "G_1") (pintype "passive"))
      (node (ref "R27") (pin "2") (pinfunction "2_2") (pintype "passive"))
      (node (ref "T1") (pin "C") (pinfunction "C_C") (pintype "passive"))
    )
    (net (code "69") (name "Net-(R26-Pad1)") (class "Default")
      (node (ref "R26") (pin "1") (pinfunction "1_1") (pintype "passive"))
      (node (ref "T1") (pin "B") (pinfunction "B_B") (pintype "passive"))
    )
    (net (code "70") (name "Net-(U1-CAP-A)") (class "Default")
      (node (ref "C13") (pin "1") (pinfunction "1_1") (pintype "passive"))
      (node (ref "U1") (pin "1") (pinfunction "CAP-A_1") (pintype "bidirectional"))
    )
    (net (code "71") (name "Net-(U1-CAP-R)") (class "Default")
      (node (ref "C14") (pin "1") (pinfunction "1_1") (pintype "passive"))
      (node (ref "U1") (pin "4") (pinfunction "CAP-R_4") (pintype "bidirectional"))
    )
    (net (code "72") (name "Net-(U2-CPOUT)") (class "Default")
      (node (ref "C12") (pin "1") (pinfunction "1_1") (pintype "passive"))
      (node (ref "U2") (pin "20") (pinfunction "CPOUT_20") (pintype "bidirectional"))
    )
    (net (code "73") (name "Net-(U2-REGOUT)") (class "Default")
      (node (ref "C11") (pin "1") (pinfunction "1_1") (pintype "passive"))
      (node (ref "U2") (pin "10") (pinfunction "REGOUT_10") (pintype "bidirectional"))
    )
    (net (code "74") (name "Net-(U3-C+)") (class "Default")
      (node (ref "C29") (pin "2") (pinfunction "2_2") (pintype "passive"))
      (node (ref "U3") (pin "6") (pinfunction "C+_6") (pintype "bidirectional"))
    )
    (net (code "75") (name "Net-(U3-C-)") (class "Default")
      (node (ref "C29") (pin "1") (pinfunction "1_1") (pintype "passive"))
      (node (ref "U3") (pin "5") (pinfunction "C-_5") (pintype "bidirectional"))
    )
    (net (code "76") (name "Net-(U3-PGOOD)") (class "Default")
      (node (ref "R30") (pin "1") (pinfunction "1_1") (pintype "passive"))
      (node (ref "U3") (pin "1") (pinfunction "PGOOD_1") (pintype "output"))
    )
    (net (code "77") (name "Net-(U4-CAP)") (class "Default")
      (node (ref "C4") (pin "1") (pinfunction "1_1") (pintype "passive"))
      (node (ref "U4") (pin "2") (pinfunction "CAP_2") (pintype "bidirectional"))
    )
    (net (code "78") (name "VCC") (class "Default")
      (node (ref "C27") (pin "1") (pinfunction "1_1") (pintype "passive"))
      (node (ref "D1") (pin "C") (pinfunction "C_C") (pintype "passive"))
      (node (ref "D2") (pin "C") (pinfunction "C_C") (pintype "passive"))
      (node (ref "D3") (pin "C") (pinfunction "C_C") (pintype "passive"))
      (node (ref "D4") (pin "C") (pinfunction "C_C") (pintype "passive"))
      (node (ref "JP1") (pin "P$2") (pinfunction "2_P$2") (pintype "passive"))
      (node (ref "JP2") (pin "P$2") (pinfunction "2_P$2") (pintype "passive"))
      (node (ref "JP3") (pin "P$2") (pinfunction "2_P$2") (pintype "passive"))
      (node (ref "JP4") (pin "P$2") (pinfunction "2_P$2") (pintype "passive"))
      (node (ref "R28") (pin "2") (pinfunction "2_2") (pintype "passive"))
      (node (ref "R30") (pin "2") (pinfunction "2_2") (pintype "passive"))
      (node (ref "SW") (pin "1") (pinfunction "O_1") (pintype "passive"))
      (node (ref "U3") (pin "3") (pinfunction "VIN_3") (pintype "power_in"))
      (node (ref "U3") (pin "7") (pinfunction "SHDN_7") (pintype "input"))
    )
    (net (code "79") (name "unconnected-(EXP1-CLKOUT-PadP$9)") (class "Default")
      (node (ref "EXP1") (pin "P$9") (pinfunction "CLKOUT_P$9") (pintype "bidirectional"))
    )
    (net (code "80") (name "unconnected-(IC2-RC13-Pad47)") (class "Default")
      (node (ref "IC2") (pin "47") (pinfunction "RC13_47") (pintype "bidirectional"))
    )
    (net (code "81") (name "unconnected-(IC2-RC14-Pad48)") (class "Default")
      (node (ref "IC2") (pin "48") (pinfunction "RC14_48") (pintype "bidirectional"))
    )
    (net (code "82") (name "unconnected-(IC2-RD6-Pad54)") (class "Default")
      (node (ref "IC2") (pin "54") (pinfunction "RD6_54") (pintype "bidirectional"))
    )
    (net (code "83") (name "unconnected-(IC2-RD7-Pad55)") (class "Default")
      (node (ref "IC2") (pin "55") (pinfunction "RD7_55") (pintype "bidirectional"))
    )
    (net (code "84") (name "unconnected-(IC2-RE0-Pad60)") (class "Default")
      (node (ref "IC2") (pin "60") (pinfunction "RE0_60") (pintype "bidirectional"))
    )
    (net (code "85") (name "unconnected-(IC2-RE1-Pad61)") (class "Default")
      (node (ref "IC2") (pin "61") (pinfunction "RE1_61") (pintype "bidirectional"))
    )
    (net (code "86") (name "unconnected-(IC2-RE2-Pad62)") (class "Default")
      (node (ref "IC2") (pin "62") (pinfunction "RE2_62") (pintype "bidirectional"))
    )
    (net (code "87") (name "unconnected-(IC2-RE5-Pad1)") (class "Default")
      (node (ref "IC2") (pin "1") (pinfunction "RE5_1") (pintype "bidirectional"))
    )
    (net (code "88") (name "unconnected-(IC2-RF0-Pad58)") (class "Default")
      (node (ref "IC2") (pin "58") (pinfunction "RF0_58") (pintype "bidirectional"))
    )
    (net (code "89") (name "unconnected-(IC2-RF1-Pad59)") (class "Default")
      (node (ref "IC2") (pin "59") (pinfunction "RF1_59") (pintype "bidirectional"))
    )
    (net (code "90") (name "unconnected-(IC2-TDI-Pad28)") (class "Default")
      (node (ref "IC2") (pin "28") (pinfunction "TDI_28") (pintype "input"))
    )
    (net (code "91") (name "unconnected-(IC2-TDO-Pad24)") (class "Default")
      (node (ref "IC2") (pin "24") (pinfunction "TDO_24") (pintype "output"))
    )
    (net (code "92") (name "unconnected-(ICSP-Pad6)") (class "Default")
      (node (ref "ICSP") (pin "6") (pinfunction "6_6") (pintype "passive"))
    )
    (net (code "93") (name "unconnected-(SW-S-Pad3)") (class "Default")
      (node (ref "SW") (pin "3") (pinfunction "S_3") (pintype "passive"))
    )
    (net (code "94") (name "unconnected-(U2-CLKOUT-Pad22)") (class "Default")
      (node (ref "U2") (pin "22") (pinfunction "CLKOUT_22") (pintype "bidirectional"))
    )
    (net (code "95") (name "unconnected-(U4-NC{slash}DOUT-Pad6)") (class "Default")
      (node (ref "U4") (pin "6") (pinfunction "NC/DOUT_6") (pintype "bidirectional"))
    )
  )
)
